# 3_STM32_MCU.net
KiCad netlist of a schematic drawn in Altium Designer
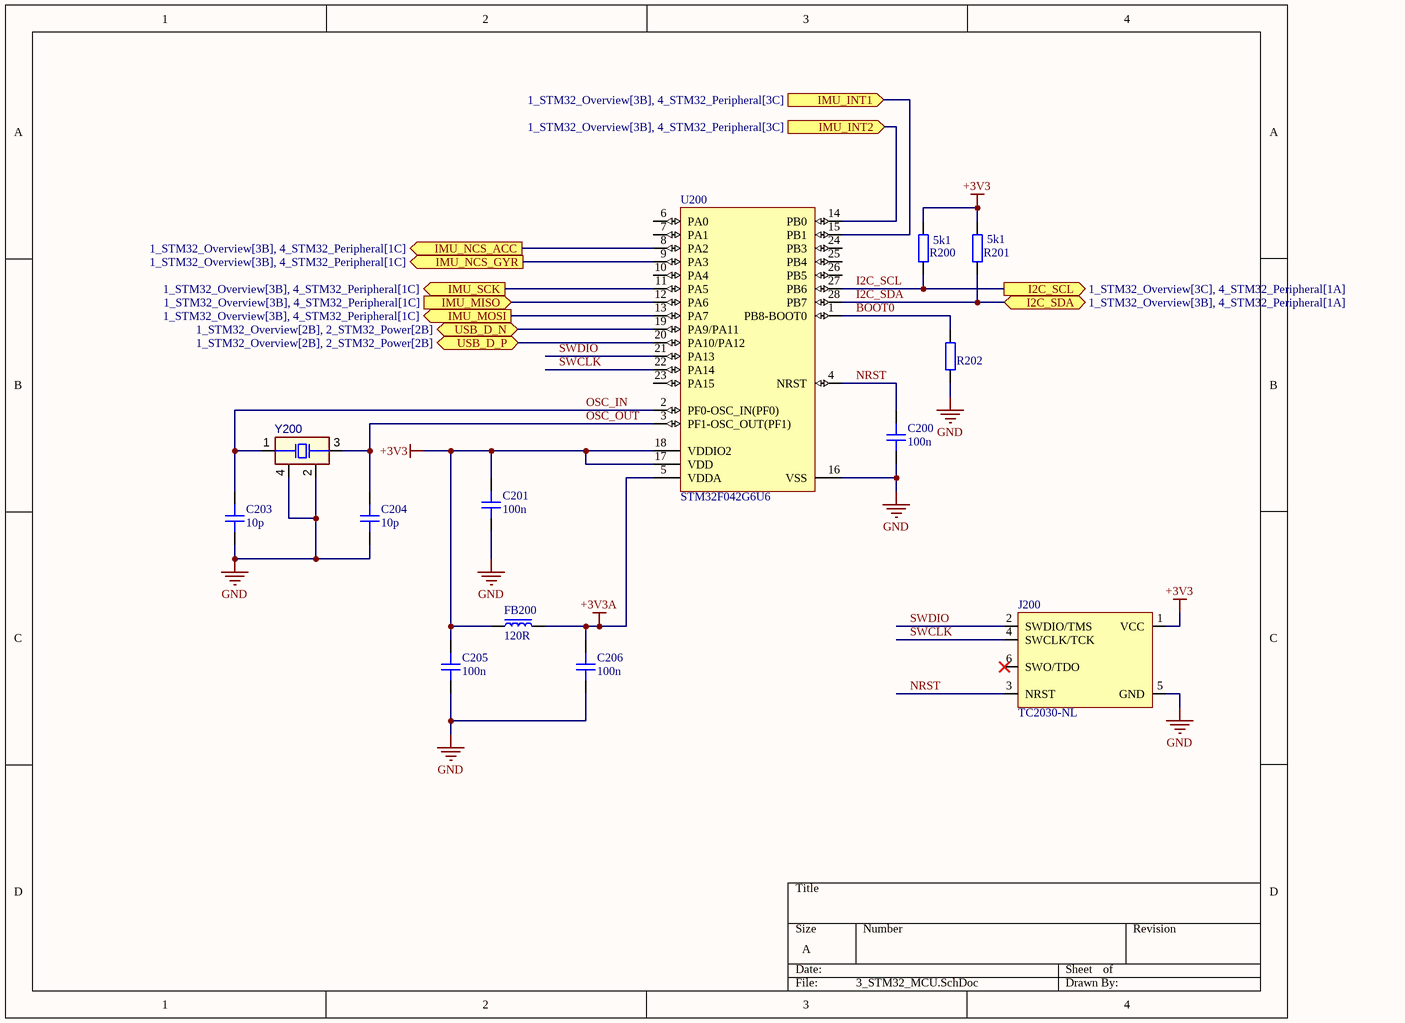
[diagram p0: 3_STM32_MCU.SchDoc]

(export (version "E")
  (design (tool "Eeschema 10.0.6"))
  (components
    (comp (ref "C200")
      (value "100n")
      (footprint "CAP_0603")
      (description "Capacitor SMD 0603")
      (libsource (lib "Schematic-Lib-PhilsLab") (part "CAP_0603"))
    )
    (comp (ref "C201")
      (value "100n")
      (footprint "CAP_0603")
      (description "Capacitor SMD 0603")
      (libsource (lib "Schematic-Lib-PhilsLab") (part "CAP_0603"))
    )
    (comp (ref "C203")
      (value "10p")
      (footprint "CAP_0603")
      (description "Capacitor SMD 0603")
      (fields (field (name "SOURCE") "Schematic-Lib-PhilsLab.SchLib"))
      (libsource (lib "Industrial University of Ho Chi Minh City") (part "CAP_EL_NP_5MM"))
    )
    (comp (ref "C204")
      (value "10p")
      (footprint "CAP_0603")
      (description "Capacitor SMD 0603")
      (fields (field (name "SOURCE") "Schematic-Lib-PhilsLab.SchLib"))
      (libsource (lib "Industrial University of Ho Chi Minh City") (part "CAP_EL_NP_5MM"))
    )
    (comp (ref "C205")
      (value "100n")
      (footprint "CAP_0603")
      (description "Capacitor SMD 0603")
      (libsource (lib "Schematic-Lib-PhilsLab") (part "CAP_0603"))
    )
    (comp (ref "C206")
      (value "100n")
      (footprint "CAP_0603")
      (description "Capacitor SMD 0603")
      (libsource (lib "Schematic-Lib-PhilsLab") (part "CAP_0603"))
    )
    (comp (ref "FB200")
      (value "120R")
      (footprint "FB_0603")
      (description "Ferrite Bead SMD 0603")
      (libsource (lib "Schematic-Lib-PhilsLab") (part "FB_0603"))
    )
    (comp (ref "J200")
      (value "TC2030-NL")
      (footprint "TC2030-NL-FP")
      (description "Tag-Connect No-Solder SWD Debug Connector (No Legs) DO NOT PLACE")
      (fields
        (field (name "MANUFACTURER") "Tag-Connect")
        (field (name "MANUFACTURER PART NUMBER") "TC2030-NL-FP")
        (field (name "SOURCE") "Schematic-Lib-PhilsLab.SchLib")
      )
      (libsource (lib "Industrial University of Ho Chi Minh City") (part "TC2030-NL"))
    )
    (comp (ref "R200")
      (value "5k1")
      (footprint "RES_0603")
      (description "Resistor SMD 0603")
      (fields (field (name "SOURCE") "Schematic-Lib-PhilsLab.SchLib"))
      (libsource (lib "Industrial University of Ho Chi Minh City") (part "RES_5931"))
    )
    (comp (ref "R201")
      (value "5k1")
      (footprint "RES_0603")
      (description "Resistor SMD 0603")
      (fields (field (name "SOURCE") "Schematic-Lib-PhilsLab.SchLib"))
      (libsource (lib "Industrial University of Ho Chi Minh City") (part "RES_5931"))
    )
    (comp (ref "R202")
      (value "5k1")
      (footprint "RES_0603")
      (description "Resistor SMD 0603")
      (fields (field (name "SOURCE") "Schematic-Lib-PhilsLab.SchLib"))
      (libsource (lib "Industrial University of Ho Chi Minh City") (part "RES_5931"))
    )
    (comp (ref "U200")
      (value "STM32F042G6U6")
      (footprint "STM-UFQFPN28_V")
      (fields (field (name "MANUFACTURER") "STMicroelectronics"))
      (libsource (lib "Altium Content Vault") (part "MC-ARM-STM32F042-UFQFPN28"))
    )
    (comp (ref "Y200")
      (value "FA-12824.0000MF10Z-W3")
      (footprint "EPSON-FA-128_V")
      (description "Crystal, 24 MHz, +/- 10 ppm, -20 to 75 degC, 4-Pin SMD, RoHS, Tape and Reel")
      (libsource (lib "Industrial University of Ho Chi Minh City") (part "CMP-00014-7"))
    )
  )
  (nets
    (net (code "1") (name "+3V3") (class "Default")
      (node (ref "C201") (pin "2") (pinfunction "2_2") (pintype "passive"))
      (node (ref "C205") (pin "2") (pinfunction "2_2") (pintype "passive"))
      (node (ref "FB200") (pin "1") (pinfunction "1_1") (pintype "passive"))
      (node (ref "J200") (pin "1") (pinfunction "VCC_1") (pintype "passive"))
      (node (ref "R200") (pin "2") (pinfunction "2_2") (pintype "passive"))
      (node (ref "R201") (pin "2") (pinfunction "2_2") (pintype "passive"))
      (node (ref "U200") (pin "17") (pinfunction "VDD_17") (pintype "power_in"))
      (node (ref "U200") (pin "18") (pinfunction "VDDIO2_18") (pintype "power_in"))
    )
    (net (code "2") (name "+3V3A") (class "Default")
      (node (ref "C206") (pin "2") (pinfunction "2_2") (pintype "passive"))
      (node (ref "FB200") (pin "2") (pinfunction "2_2") (pintype "passive"))
      (node (ref "U200") (pin "5") (pinfunction "VDDA_5") (pintype "power_in"))
    )
    (net (code "3") (name "/BOOT0") (class "Default")
      (node (ref "R202") (pin "1") (pinfunction "1_1") (pintype "passive"))
      (node (ref "U200") (pin "1") (pinfunction "PB8-BOOT0_1") (pintype "bidirectional"))
    )
    (net (code "4") (name "/I2C_SCL") (class "Default")
      (node (ref "R200") (pin "1") (pinfunction "1_1") (pintype "passive"))
      (node (ref "U200") (pin "27") (pinfunction "PB6_27") (pintype "bidirectional"))
    )
    (net (code "5") (name "/I2C_SDA") (class "Default")
      (node (ref "R201") (pin "1") (pinfunction "1_1") (pintype "passive"))
      (node (ref "U200") (pin "28") (pinfunction "PB7_28") (pintype "bidirectional"))
    )
    (net (code "6") (name "/IMU_INT1") (class "Default")
      (node (ref "U200") (pin "15") (pinfunction "PB1_15") (pintype "bidirectional"))
    )
    (net (code "7") (name "/IMU_INT2") (class "Default")
      (node (ref "U200") (pin "14") (pinfunction "PB0_14") (pintype "bidirectional"))
    )
    (net (code "8") (name "/IMU_MISO") (class "Default")
      (node (ref "U200") (pin "12") (pinfunction "PA6_12") (pintype "bidirectional"))
    )
    (net (code "9") (name "/IMU_MOSI") (class "Default")
      (node (ref "U200") (pin "13") (pinfunction "PA7_13") (pintype "bidirectional"))
    )
    (net (code "10") (name "/IMU_NCS_ACC") (class "Default")
      (node (ref "U200") (pin "8") (pinfunction "PA2_8") (pintype "bidirectional"))
    )
    (net (code "11") (name "/IMU_NCS_GYR") (class "Default")
      (node (ref "U200") (pin "9") (pinfunction "PA3_9") (pintype "bidirectional"))
    )
    (net (code "12") (name "/IMU_SCK") (class "Default")
      (node (ref "U200") (pin "11") (pinfunction "PA5_11") (pintype "bidirectional"))
    )
    (net (code "13") (name "/NRST") (class "Default")
      (node (ref "C200") (pin "2") (pinfunction "2_2") (pintype "passive"))
      (node (ref "J200") (pin "3") (pinfunction "NRST_3") (pintype "passive"))
      (node (ref "U200") (pin "4") (pinfunction "NRST_4") (pintype "bidirectional"))
    )
    (net (code "14") (name "/OSC_IN") (class "Default")
      (node (ref "C203") (pin "2") (pinfunction "2_2") (pintype "passive"))
      (node (ref "U200") (pin "2") (pinfunction "PF0-OSC_IN(PF0)_2") (pintype "bidirectional"))
      (node (ref "Y200") (pin "1") (pinfunction "X1_1") (pintype "passive"))
    )
    (net (code "15") (name "/OSC_OUT") (class "Default")
      (node (ref "C204") (pin "2") (pinfunction "2_2") (pintype "passive"))
      (node (ref "U200") (pin "3") (pinfunction "PF1-OSC_OUT(PF1)_3") (pintype "bidirectional"))
      (node (ref "Y200") (pin "3") (pinfunction "X2_3") (pintype "passive"))
    )
    (net (code "16") (name "/SWCLK") (class "Default")
      (node (ref "J200") (pin "4") (pinfunction "SWCLK/TCK_4") (pintype "passive"))
      (node (ref "U200") (pin "22") (pinfunction "PA14_22") (pintype "bidirectional"))
    )
    (net (code "17") (name "/SWDIO") (class "Default")
      (node (ref "J200") (pin "2") (pinfunction "SWDIO/TMS_2") (pintype "passive"))
      (node (ref "U200") (pin "21") (pinfunction "PA13_21") (pintype "bidirectional"))
    )
    (net (code "18") (name "/USB_D_N") (class "Default")
      (node (ref "U200") (pin "19") (pinfunction "PA9/PA11_19") (pintype "bidirectional"))
    )
    (net (code "19") (name "/USB_D_P") (class "Default")
      (node (ref "U200") (pin "20") (pinfunction "PA10/PA12_20") (pintype "bidirectional"))
    )
    (net (code "20") (name "GND") (class "Default")
      (node (ref "C200") (pin "1") (pinfunction "1_1") (pintype "passive"))
      (node (ref "C201") (pin "1") (pinfunction "1_1") (pintype "passive"))
      (node (ref "C203") (pin "1") (pinfunction "1_1") (pintype "passive"))
      (node (ref "C204") (pin "1") (pinfunction "1_1") (pintype "passive"))
      (node (ref "C205") (pin "1") (pinfunction "1_1") (pintype "passive"))
      (node (ref "C206") (pin "1") (pinfunction "1_1") (pintype "passive"))
      (node (ref "J200") (pin "5") (pinfunction "GND_5") (pintype "passive"))
      (node (ref "R202") (pin "2") (pinfunction "2_2") (pintype "passive"))
      (node (ref "U200") (pin "16") (pinfunction "VSS_16") (pintype "power_in"))
      (node (ref "Y200") (pin "2") (pinfunction "NC_2") (pintype "power_in"))
      (node (ref "Y200") (pin "4") (pinfunction "NC_4") (pintype "power_in"))
    )
    (net (code "21") (name "unconnected-(J200-SWO{slash}TDO-Pad6)") (class "Default")
      (node (ref "J200") (pin "6") (pinfunction "SWO/TDO_6") (pintype "passive+no_connect"))
    )
    (net (code "22") (name "unconnected-(U200-PA0-Pad6)") (class "Default")
      (node (ref "U200") (pin "6") (pinfunction "PA0_6") (pintype "bidirectional"))
    )
    (net (code "23") (name "unconnected-(U200-PA1-Pad7)") (class "Default")
      (node (ref "U200") (pin "7") (pinfunction "PA1_7") (pintype "bidirectional"))
    )
    (net (code "24") (name "unconnected-(U200-PA4-Pad10)") (class "Default")
      (node (ref "U200") (pin "10") (pinfunction "PA4_10") (pintype "bidirectional"))
    )
    (net (code "25") (name "unconnected-(U200-PA15-Pad23)") (class "Default")
      (node (ref "U200") (pin "23") (pinfunction "PA15_23") (pintype "bidirectional"))
    )
    (net (code "26") (name "unconnected-(U200-PB3-Pad24)") (class "Default")
      (node (ref "U200") (pin "24") (pinfunction "PB3_24") (pintype "bidirectional"))
    )
    (net (code "27") (name "unconnected-(U200-PB4-Pad25)") (class "Default")
      (node (ref "U200") (pin "25") (pinfunction "PB4_25") (pintype "bidirectional"))
    )
    (net (code "28") (name "unconnected-(U200-PB5-Pad26)") (class "Default")
      (node (ref "U200") (pin "26") (pinfunction "PB5_26") (pintype "bidirectional"))
    )
  )
)
